# Accessories.net
KiCad netlist of a schematic drawn in Altium Designer
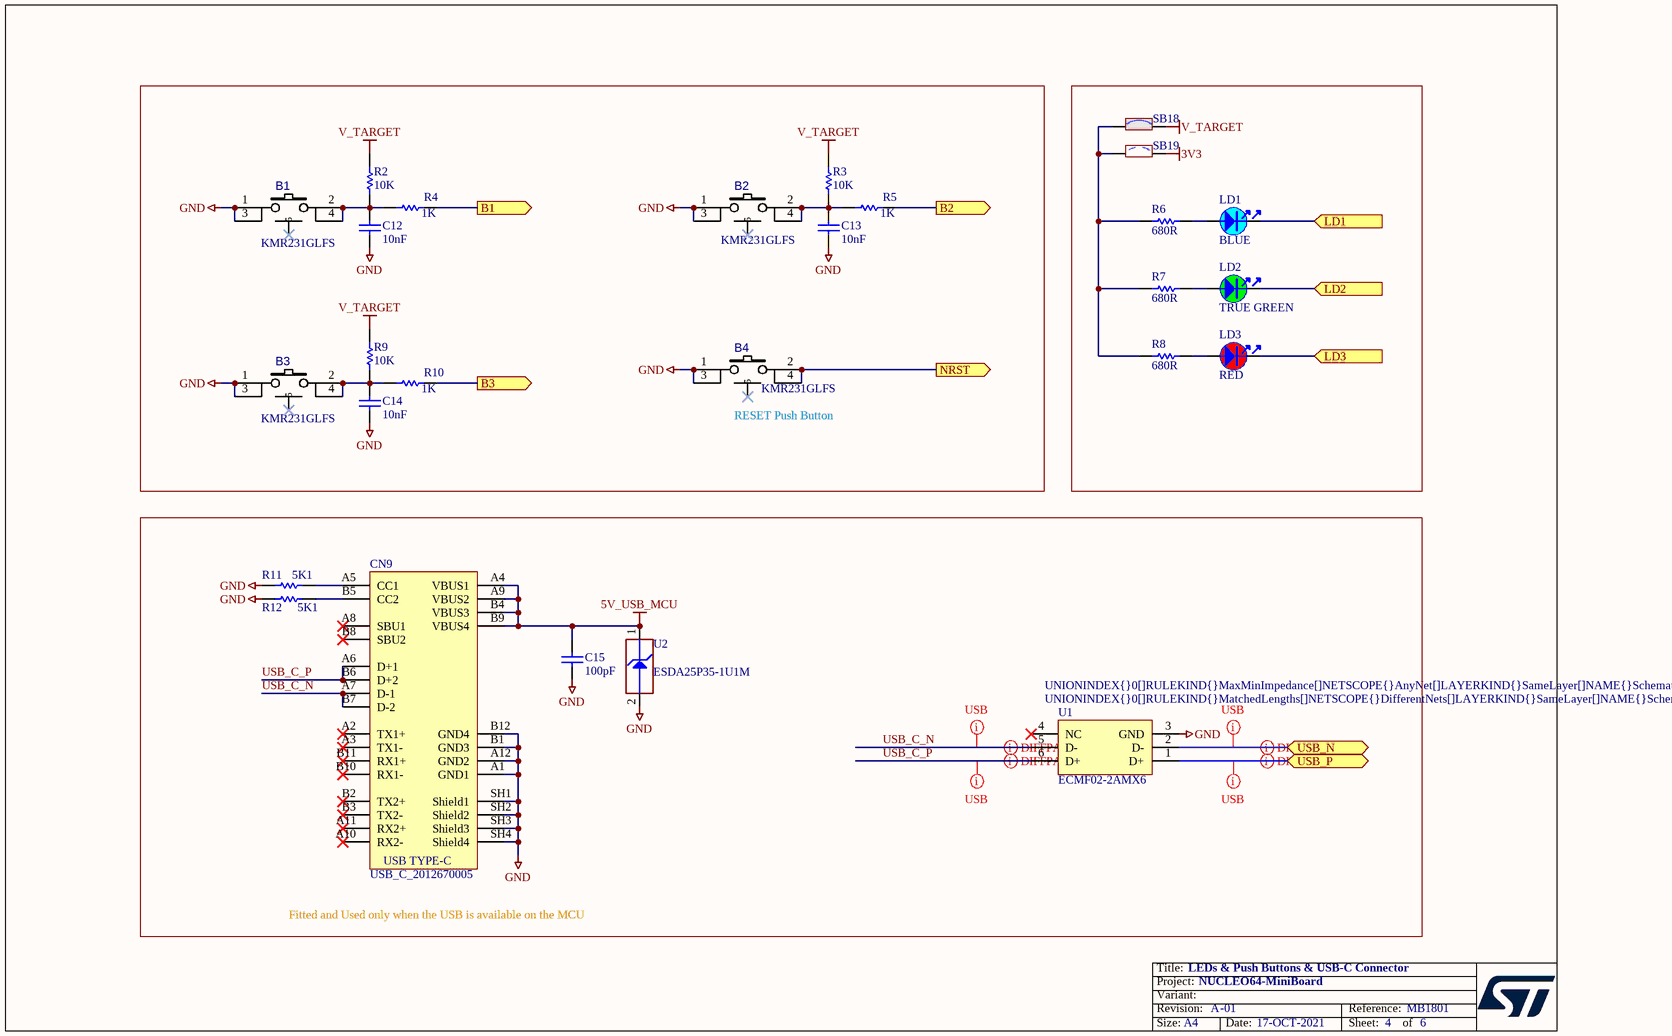
[diagram p0: Accessories.SchDoc]

(export (version "E")
  (design (tool "Eeschema 10.0.6"))
  (components
    (comp (ref "B1")
      (value "KMR231GLFS")
      (footprint "SWI_C&K_Y78B23110FP__ITT_KMR231GLFS")
      (description "Microminiature Tact Switch for SMT - KMR 2 Series - 1.9 mm height")
      (fields (field (name "INTERNAL_PART_NUMBER") "MCD-01485") (field (name "MANUFACTURER") "C&K"))
      (libsource (lib "MCD_PARTS_database") (part "SW-PUSH-CMS_KMR2_BLACK"))
    )
    (comp (ref "B2")
      (value "KMR231GLFS")
      (footprint "SWI_C&K_Y78B23110FP__ITT_KMR231GLFS")
      (description "Microminiature Tact Switch for SMT - KMR 2 Series - 1.9 mm height")
      (fields (field (name "INTERNAL_PART_NUMBER") "MCD-01485") (field (name "MANUFACTURER") "C&K"))
      (libsource (lib "MCD_PARTS_database") (part "SW-PUSH-CMS_KMR2_BLACK"))
    )
    (comp (ref "B3")
      (value "KMR231GLFS")
      (footprint "SWI_C&K_Y78B23110FP__ITT_KMR231GLFS")
      (description "Microminiature Tact Switch for SMT - KMR 2 Series - 1.9 mm height")
      (fields (field (name "INTERNAL_PART_NUMBER") "MCD-01485") (field (name "MANUFACTURER") "C&K"))
      (libsource (lib "MCD_PARTS_database") (part "SW-PUSH-CMS_KMR2_BLACK"))
    )
    (comp (ref "B4")
      (value "KMR231GLFS")
      (footprint "SWI_C&K_Y78B23110FP__ITT_KMR231GLFS")
      (description "Microminiature Tact Switch for SMT - KMR 2 Series - 1.9 mm height")
      (fields (field (name "INTERNAL_PART_NUMBER") "MCD-01485") (field (name "MANUFACTURER") "C&K"))
      (libsource (lib "MCD_PARTS_database") (part "SW-PUSH-CMS_KMR2_BLACK"))
    )
    (comp (ref "C12")
      (value "10nF")
      (footprint "C0402")
      (description "Capacitor, MLCC, 10nF, 50V, X7R, +/-10%, 0402, T=0.5mm")
      (fields (field (name "INTERNAL_PART_NUMBER") "MCD-02198") (field (name "MANUFACTURER") "YAGEO"))
      (libsource (lib "MCD_PARTS_database") (part "Capacitor"))
    )
    (comp (ref "C13")
      (value "10nF")
      (footprint "C0402")
      (description "Capacitor, MLCC, 10nF, 50V, X7R, +/-10%, 0402, T=0.5mm")
      (fields (field (name "INTERNAL_PART_NUMBER") "MCD-02198") (field (name "MANUFACTURER") "YAGEO"))
      (libsource (lib "MCD_PARTS_database") (part "Capacitor"))
    )
    (comp (ref "C14")
      (value "10nF")
      (footprint "C0402")
      (description "Capacitor, MLCC, 10nF, 50V, X7R, +/-10%, 0402, T=0.5mm")
      (fields (field (name "INTERNAL_PART_NUMBER") "MCD-02198") (field (name "MANUFACTURER") "YAGEO"))
      (libsource (lib "MCD_PARTS_database") (part "Capacitor"))
    )
    (comp (ref "C15")
      (value "100pF")
      (footprint "C0402")
      (description "Capacitor, MLCC, 100pF, 50V, NPO, +/-5%, 0402, T=0.5mm")
      (fields
        (field (name "INTERNAL_PART_NUMBER") "MCD-00205")
        (field (name "MANUFACTURER_PART_NUMBER") "CC0402JRNPO9BN101")
      )
      (libsource (lib "MCD_PARTS_database") (part "Capacitor"))
    )
    (comp (ref "CN9")
      (value "USB_C_2012670005")
      (footprint "CON_USB-TYPEC_MOLEX_2012670005")
      (description "USB_TypeC, 24 pins, RA, SMD, T=3.71mm (USB Certified 3.1)")
      (fields (field (name "INTERNAL_PART_NUMBER") "MCD-02421") (field (name "MANUFACTURER") "MOLEX"))
      (libsource (lib "MCD_PARTS_database") (part "USB_TYPE_C_Receptacle"))
    )
    (comp (ref "LD1")
      (value "BLUE")
      (footprint "LED_0603_VISHAY_VLMB1300-GS08_BLUE_1A2K_H0P8")
      (description "LED Blue, 0603 SMD, 3.3 V Forward Voltage")
      (fields
        (field (name "INTERNAL_PART_NUMBER") "MCD-00584")
        (field (name "MANUFACTURER_PART_NUMBER") "VLMB1300-GS08")
      )
      (libsource (lib "MCD_PARTS_database") (part "LED_blue"))
    )
    (comp (ref "LD2")
      (value "TRUE GREEN")
      (footprint "LED_0603_VISHAY_VLMTG1300-GS08_GREEN_1A2K_H0P8")
      (description "LED Green, 0603 SMD, Fw Voltage = 2.8V - 3.6V")
      (fields
        (field (name "INTERNAL_PART_NUMBER") "MCD-00589")
        (field (name "MANUFACTURER_PART_NUMBER") "VLMTG1300-GS08")
      )
      (libsource (lib "MCD_PARTS_database") (part "LED_green"))
    )
    (comp (ref "LD3")
      (value "RED")
      (footprint "LED_0603_VISHAY_VLMS1300-GS08_RED_1A2K_H0P8")
      (description "LED Red, 0603 SMD, 2V Forward Voltage")
      (fields
        (field (name "INTERNAL_PART_NUMBER") "MCD-00587")
        (field (name "MANUFACTURER_PART_NUMBER") "VLMS1300-GS08")
      )
      (libsource (lib "MCD_PARTS_database") (part "LED_red"))
    )
    (comp (ref "R2")
      (value "10K")
      (footprint "R0402")
      (description "Resistor, 10K, 0402, +/-1%, 1/16W")
      (fields (field (name "INTERNAL_PART_NUMBER") "MCD-00053") (field (name "BMS_PART_NUMBER") "9131590"))
      (libsource (lib "MCD_PARTS_database") (part "Resistor"))
    )
    (comp (ref "R3")
      (value "10K")
      (footprint "R0402")
      (description "Resistor, 10K, 0402, +/-1%, 1/16W")
      (fields (field (name "INTERNAL_PART_NUMBER") "MCD-00053") (field (name "BMS_PART_NUMBER") "9131590"))
      (libsource (lib "MCD_PARTS_database") (part "Resistor"))
    )
    (comp (ref "R4")
      (value "1K")
      (footprint "R0402")
      (description "Resistor, 1K, 0402, +/-1%,1/16W")
      (fields
        (field (name "INTERNAL_PART_NUMBER") "MCD-00061")
        (field (name "MANUFACTURER_PART_NUMBER") "RC0402FR-071KL")
      )
      (libsource (lib "MCD_PARTS_database") (part "Resistor"))
    )
    (comp (ref "R5")
      (value "1K")
      (footprint "R0402")
      (description "Resistor, 1K, 0402, +/-1%,1/16W")
      (fields
        (field (name "INTERNAL_PART_NUMBER") "MCD-00061")
        (field (name "MANUFACTURER_PART_NUMBER") "RC0402FR-071KL")
      )
      (libsource (lib "MCD_PARTS_database") (part "Resistor"))
    )
    (comp (ref "R6")
      (value "680R")
      (footprint "R0402")
      (description "Resistor, 680R, 0402, +/-1%, 1/16W")
      (fields
        (field (name "INTERNAL_PART_NUMBER") "MCD-00507")
        (field (name "MANUFACTURER_PART_NUMBER") "RC0402FR-07680RL")
      )
      (libsource (lib "MCD_PARTS_database") (part "Resistor"))
    )
    (comp (ref "R7")
      (value "680R")
      (footprint "R0402")
      (description "Resistor, 680R, 0402, +/-1%, 1/16W")
      (fields
        (field (name "INTERNAL_PART_NUMBER") "MCD-00507")
        (field (name "MANUFACTURER_PART_NUMBER") "RC0402FR-07680RL")
      )
      (libsource (lib "MCD_PARTS_database") (part "Resistor"))
    )
    (comp (ref "R8")
      (value "680R")
      (footprint "R0402")
      (description "Resistor, 680R, 0402, +/-1%, 1/16W")
      (fields
        (field (name "INTERNAL_PART_NUMBER") "MCD-00507")
        (field (name "MANUFACTURER_PART_NUMBER") "RC0402FR-07680RL")
      )
      (libsource (lib "MCD_PARTS_database") (part "Resistor"))
    )
    (comp (ref "R9")
      (value "10K")
      (footprint "R0402")
      (description "Resistor, 10K, 0402, +/-1%, 1/16W")
      (fields (field (name "INTERNAL_PART_NUMBER") "MCD-00053") (field (name "BMS_PART_NUMBER") "9131590"))
      (libsource (lib "MCD_PARTS_database") (part "Resistor"))
    )
    (comp (ref "R10")
      (value "1K")
      (footprint "R0402")
      (description "Resistor, 1K, 0402, +/-1%,1/16W")
      (fields
        (field (name "INTERNAL_PART_NUMBER") "MCD-00061")
        (field (name "MANUFACTURER_PART_NUMBER") "RC0402FR-071KL")
      )
      (libsource (lib "MCD_PARTS_database") (part "Resistor"))
    )
    (comp (ref "R11")
      (value "5K1")
      (footprint "R0402")
      (description "Resistor, 5K1, 0402, +/-1%, 1/16W")
      (fields
        (field (name "INTERNAL_PART_NUMBER") "MCD-00333")
        (field (name "MANUFACTURER_PART_NUMBER") "RC0402FR-075K1L")
      )
      (libsource (lib "MCD_PARTS_database") (part "Resistor"))
    )
    (comp (ref "R12")
      (value "5K1")
      (footprint "R0402")
      (description "Resistor, 5K1, 0402, +/-1%, 1/16W")
      (fields
        (field (name "INTERNAL_PART_NUMBER") "MCD-00333")
        (field (name "MANUFACTURER_PART_NUMBER") "RC0402FR-075K1L")
      )
      (libsource (lib "MCD_PARTS_database") (part "Resistor"))
    )
    (comp (ref "SB18")
      (value "SB_ON")
      (footprint "SOLDER-BRIDGE_R0402-0R")
      (description "Solder Bridge 0402 ON")
      (fields (field (name "INTERNAL_PART_NUMBER") "MCD-01618") (field (name "MANUFACTURER") "YAGEO"))
      (libsource (lib "MCD_PARTS_database") (part "SB_ON"))
    )
    (comp (ref "SB19")
      (value "SB_OFF")
      (footprint "SOLDER-BRIDGE_R0402-0R")
      (description "Solder Bridge 0402 OFF")
      (fields (field (name "INTERNAL_PART_NUMBER") "MCD-02162") (field (name "MANUFACTURER") "YAGEO"))
      (libsource (lib "MCD_PARTS_database") (part "SB_OFF"))
    )
    (comp (ref "U1")
      (value "ECMF02-2AMX6")
      (footprint "ESD_QFN-6L_1P7X1P5_P050")
      (description "Common mode filter with ESD protection for USB 2.0 interface")
      (fields
        (field (name "INTERNAL_PART_NUMBER") "MCD-00649")
        (field (name "MANUFACTURER") "STMICROELECTRONICS")
      )
      (libsource (lib "MCD_PARTS_database") (part "ECMF02-2AMX6"))
    )
    (comp (ref "U2")
      (value "ESDA25P35-1U1M")
      (footprint "ESD_QFN1610_2N_1K_2A")
      (description "High power Transient voltage suppressor:25V/35A EOS and ESD transients protection.")
      (fields
        (field (name "INTERNAL_PART_NUMBER") "MCD-01207")
        (field (name "MANUFACTURER") "STMICROELECTRONICS")
      )
      (libsource (lib "MCD_PARTS_database") (part "ESD-TRANSIL"))
    )
  )
  (nets
    (net (code "1") (name "/B1") (class "Default")
      (node (ref "R4") (pin "2") (pinfunction "2_2") (pintype "passive"))
    )
    (net (code "2") (name "/B2") (class "Default")
      (node (ref "R5") (pin "2") (pinfunction "2_2") (pintype "passive"))
    )
    (net (code "3") (name "/B3") (class "Default")
      (node (ref "R10") (pin "2") (pinfunction "2_2") (pintype "passive"))
    )
    (net (code "4") (name "/LD1") (class "Default") (node (ref "LD1") (pin "2") (pintype "passive")))
    (net (code "5") (name "/LD2") (class "Default") (node (ref "LD2") (pin "2") (pintype "passive")))
    (net (code "6") (name "/LD3") (class "Default") (node (ref "LD3") (pin "2") (pintype "passive")))
    (net (code "7") (name "/NRST") (class "Default")
      (node (ref "B4") (pin "2") (pinfunction "2_2") (pintype "passive"))
      (node (ref "B4") (pin "4") (pinfunction "4_4") (pintype "passive"))
    )
    (net (code "8") (name "/USB_C_N") (class "Default")
      (node (ref "CN9") (pin "A7") (pinfunction "D-1_A7") (pintype "passive"))
      (node (ref "CN9") (pin "B7") (pinfunction "D-2_B7") (pintype "passive"))
      (node (ref "U1") (pin "5") (pinfunction "D-_5") (pintype "passive"))
    )
    (net (code "9") (name "/USB_C_P") (class "Default")
      (node (ref "CN9") (pin "A6") (pinfunction "D+1_A6") (pintype "passive"))
      (node (ref "CN9") (pin "B6") (pinfunction "D+2_B6") (pintype "passive"))
      (node (ref "U1") (pin "6") (pinfunction "D+_6") (pintype "passive"))
    )
    (net (code "10") (name "/USB_N") (class "Default")
      (node (ref "U1") (pin "2") (pinfunction "D-_2") (pintype "passive"))
    )
    (net (code "11") (name "/USB_P") (class "Default")
      (node (ref "U1") (pin "1") (pinfunction "D+_1") (pintype "passive"))
    )
    (net (code "12") (name "3V3") (class "Default")
      (node (ref "SB19") (pin "2") (pinfunction "2_2") (pintype "passive"))
    )
    (net (code "13") (name "5V_USB_MCU") (class "Default")
      (node (ref "C15") (pin "2") (pinfunction "2_2") (pintype "passive"))
      (node (ref "CN9") (pin "A4") (pinfunction "VBUS1_A4") (pintype "passive"))
      (node (ref "CN9") (pin "A9") (pinfunction "VBUS2_A9") (pintype "passive"))
      (node (ref "CN9") (pin "B4") (pinfunction "VBUS3_B4") (pintype "passive"))
      (node (ref "CN9") (pin "B9") (pinfunction "VBUS4_B9") (pintype "passive"))
      (node (ref "U2") (pin "1") (pinfunction "IO1_1") (pintype "passive"))
    )
    (net (code "14") (name "GND") (class "Default")
      (node (ref "B1") (pin "1") (pinfunction "1_1") (pintype "passive"))
      (node (ref "B1") (pin "3") (pinfunction "3_3") (pintype "passive"))
      (node (ref "B2") (pin "1") (pinfunction "1_1") (pintype "passive"))
      (node (ref "B2") (pin "3") (pinfunction "3_3") (pintype "passive"))
      (node (ref "B3") (pin "1") (pinfunction "1_1") (pintype "passive"))
      (node (ref "B3") (pin "3") (pinfunction "3_3") (pintype "passive"))
      (node (ref "B4") (pin "1") (pinfunction "1_1") (pintype "passive"))
      (node (ref "B4") (pin "3") (pinfunction "3_3") (pintype "passive"))
      (node (ref "C12") (pin "1") (pinfunction "1_1") (pintype "passive"))
      (node (ref "C13") (pin "1") (pinfunction "1_1") (pintype "passive"))
      (node (ref "C14") (pin "1") (pinfunction "1_1") (pintype "passive"))
      (node (ref "C15") (pin "1") (pinfunction "1_1") (pintype "passive"))
      (node (ref "CN9") (pin "A1") (pinfunction "GND1_A1") (pintype "passive"))
      (node (ref "CN9") (pin "A12") (pinfunction "GND2_A12") (pintype "passive"))
      (node (ref "CN9") (pin "B1") (pinfunction "GND3_B1") (pintype "passive"))
      (node (ref "CN9") (pin "B12") (pinfunction "GND4_B12") (pintype "passive"))
      (node (ref "CN9") (pin "SH1") (pinfunction "Shield1_SH1") (pintype "passive"))
      (node (ref "CN9") (pin "SH2") (pinfunction "Shield2_SH2") (pintype "passive"))
      (node (ref "CN9") (pin "SH3") (pinfunction "Shield3_SH3") (pintype "passive"))
      (node (ref "CN9") (pin "SH4") (pinfunction "Shield4_SH4") (pintype "passive"))
      (node (ref "R11") (pin "1") (pinfunction "1_1") (pintype "passive"))
      (node (ref "R12") (pin "1") (pinfunction "1_1") (pintype "passive"))
      (node (ref "U1") (pin "3") (pinfunction "GND_3") (pintype "passive"))
      (node (ref "U2") (pin "2") (pinfunction "GND_2") (pintype "passive"))
    )
    (net (code "15") (name "Net-(B1-Pad2)") (class "Default")
      (node (ref "B1") (pin "2") (pinfunction "2_2") (pintype "passive"))
      (node (ref "B1") (pin "4") (pinfunction "4_4") (pintype "passive"))
      (node (ref "C12") (pin "2") (pinfunction "2_2") (pintype "passive"))
      (node (ref "R2") (pin "1") (pinfunction "1_1") (pintype "passive"))
      (node (ref "R4") (pin "1") (pinfunction "1_1") (pintype "passive"))
    )
    (net (code "16") (name "Net-(B2-Pad2)") (class "Default")
      (node (ref "B2") (pin "2") (pinfunction "2_2") (pintype "passive"))
      (node (ref "B2") (pin "4") (pinfunction "4_4") (pintype "passive"))
      (node (ref "C13") (pin "2") (pinfunction "2_2") (pintype "passive"))
      (node (ref "R3") (pin "1") (pinfunction "1_1") (pintype "passive"))
      (node (ref "R5") (pin "1") (pinfunction "1_1") (pintype "passive"))
    )
    (net (code "17") (name "Net-(B3-Pad2)") (class "Default")
      (node (ref "B3") (pin "2") (pinfunction "2_2") (pintype "passive"))
      (node (ref "B3") (pin "4") (pinfunction "4_4") (pintype "passive"))
      (node (ref "C14") (pin "2") (pinfunction "2_2") (pintype "passive"))
      (node (ref "R10") (pin "1") (pinfunction "1_1") (pintype "passive"))
      (node (ref "R9") (pin "1") (pinfunction "1_1") (pintype "passive"))
    )
    (net (code "18") (name "Net-(CN9-CC1)") (class "Default")
      (node (ref "CN9") (pin "A5") (pinfunction "CC1_A5") (pintype "passive"))
      (node (ref "R11") (pin "2") (pinfunction "2_2") (pintype "passive"))
    )
    (net (code "19") (name "Net-(CN9-CC2)") (class "Default")
      (node (ref "CN9") (pin "B5") (pinfunction "CC2_B5") (pintype "passive"))
      (node (ref "R12") (pin "2") (pinfunction "2_2") (pintype "passive"))
    )
    (net (code "20") (name "Net-(LD1-Pad1)") (class "Default")
      (node (ref "LD1") (pin "1") (pintype "passive"))
      (node (ref "R6") (pin "2") (pinfunction "2_2") (pintype "passive"))
    )
    (net (code "21") (name "Net-(LD2-Pad1)") (class "Default")
      (node (ref "LD2") (pin "1") (pintype "passive"))
      (node (ref "R7") (pin "2") (pinfunction "2_2") (pintype "passive"))
    )
    (net (code "22") (name "Net-(LD3-Pad1)") (class "Default")
      (node (ref "LD3") (pin "1") (pintype "passive"))
      (node (ref "R8") (pin "2") (pinfunction "2_2") (pintype "passive"))
    )
    (net (code "23") (name "Net-(R6-Pad1)") (class "Default")
      (node (ref "R6") (pin "1") (pinfunction "1_1") (pintype "passive"))
      (node (ref "R7") (pin "1") (pinfunction "1_1") (pintype "passive"))
      (node (ref "R8") (pin "1") (pinfunction "1_1") (pintype "passive"))
      (node (ref "SB18") (pin "1") (pinfunction "1_1") (pintype "passive"))
      (node (ref "SB19") (pin "1") (pinfunction "1_1") (pintype "passive"))
    )
    (net (code "24") (name "V_TARGET") (class "Default")
      (node (ref "R2") (pin "2") (pinfunction "2_2") (pintype "passive"))
      (node (ref "R3") (pin "2") (pinfunction "2_2") (pintype "passive"))
      (node (ref "R9") (pin "2") (pinfunction "2_2") (pintype "passive"))
      (node (ref "SB18") (pin "2") (pinfunction "2_2") (pintype "passive"))
    )
    (net (code "25") (name "unconnected-(B1-Pad5)") (class "Default")
      (node (ref "B1") (pin "5") (pinfunction "5_5") (pintype "passive+no_connect"))
    )
    (net (code "26") (name "unconnected-(B2-Pad5)") (class "Default")
      (node (ref "B2") (pin "5") (pinfunction "5_5") (pintype "passive+no_connect"))
    )
    (net (code "27") (name "unconnected-(B3-Pad5)") (class "Default")
      (node (ref "B3") (pin "5") (pinfunction "5_5") (pintype "passive+no_connect"))
    )
    (net (code "28") (name "unconnected-(B4-Pad5)") (class "Default")
      (node (ref "B4") (pin "5") (pinfunction "5_5") (pintype "passive+no_connect"))
    )
    (net (code "29") (name "unconnected-(CN9-RX1+-PadB11)") (class "Default")
      (node (ref "CN9") (pin "B11") (pinfunction "RX1+_B11") (pintype "passive+no_connect"))
    )
    (net (code "30") (name "unconnected-(CN9-RX1--PadB10)") (class "Default")
      (node (ref "CN9") (pin "B10") (pinfunction "RX1-_B10") (pintype "passive+no_connect"))
    )
    (net (code "31") (name "unconnected-(CN9-RX2+-PadA11)") (class "Default")
      (node (ref "CN9") (pin "A11") (pinfunction "RX2+_A11") (pintype "passive+no_connect"))
    )
    (net (code "32") (name "unconnected-(CN9-RX2--PadA10)") (class "Default")
      (node (ref "CN9") (pin "A10") (pinfunction "RX2-_A10") (pintype "passive+no_connect"))
    )
    (net (code "33") (name "unconnected-(CN9-SBU1-PadA8)") (class "Default")
      (node (ref "CN9") (pin "A8") (pinfunction "SBU1_A8") (pintype "passive+no_connect"))
    )
    (net (code "34") (name "unconnected-(CN9-SBU2-PadB8)") (class "Default")
      (node (ref "CN9") (pin "B8") (pinfunction "SBU2_B8") (pintype "passive+no_connect"))
    )
    (net (code "35") (name "unconnected-(CN9-TX1+-PadA2)") (class "Default")
      (node (ref "CN9") (pin "A2") (pinfunction "TX1+_A2") (pintype "passive+no_connect"))
    )
    (net (code "36") (name "unconnected-(CN9-TX1--PadA3)") (class "Default")
      (node (ref "CN9") (pin "A3") (pinfunction "TX1-_A3") (pintype "passive+no_connect"))
    )
    (net (code "37") (name "unconnected-(CN9-TX2+-PadB2)") (class "Default")
      (node (ref "CN9") (pin "B2") (pinfunction "TX2+_B2") (pintype "passive+no_connect"))
    )
    (net (code "38") (name "unconnected-(CN9-TX2--PadB3)") (class "Default")
      (node (ref "CN9") (pin "B3") (pinfunction "TX2-_B3") (pintype "passive+no_connect"))
    )
    (net (code "39") (name "unconnected-(U1-NC-Pad4)") (class "Default")
      (node (ref "U1") (pin "4") (pinfunction "NC_4") (pintype "passive+no_connect"))
    )
  )
)
